# Interface_Adapter_Mk_2.net
KiCad netlist of a schematic drawn in EAGLE
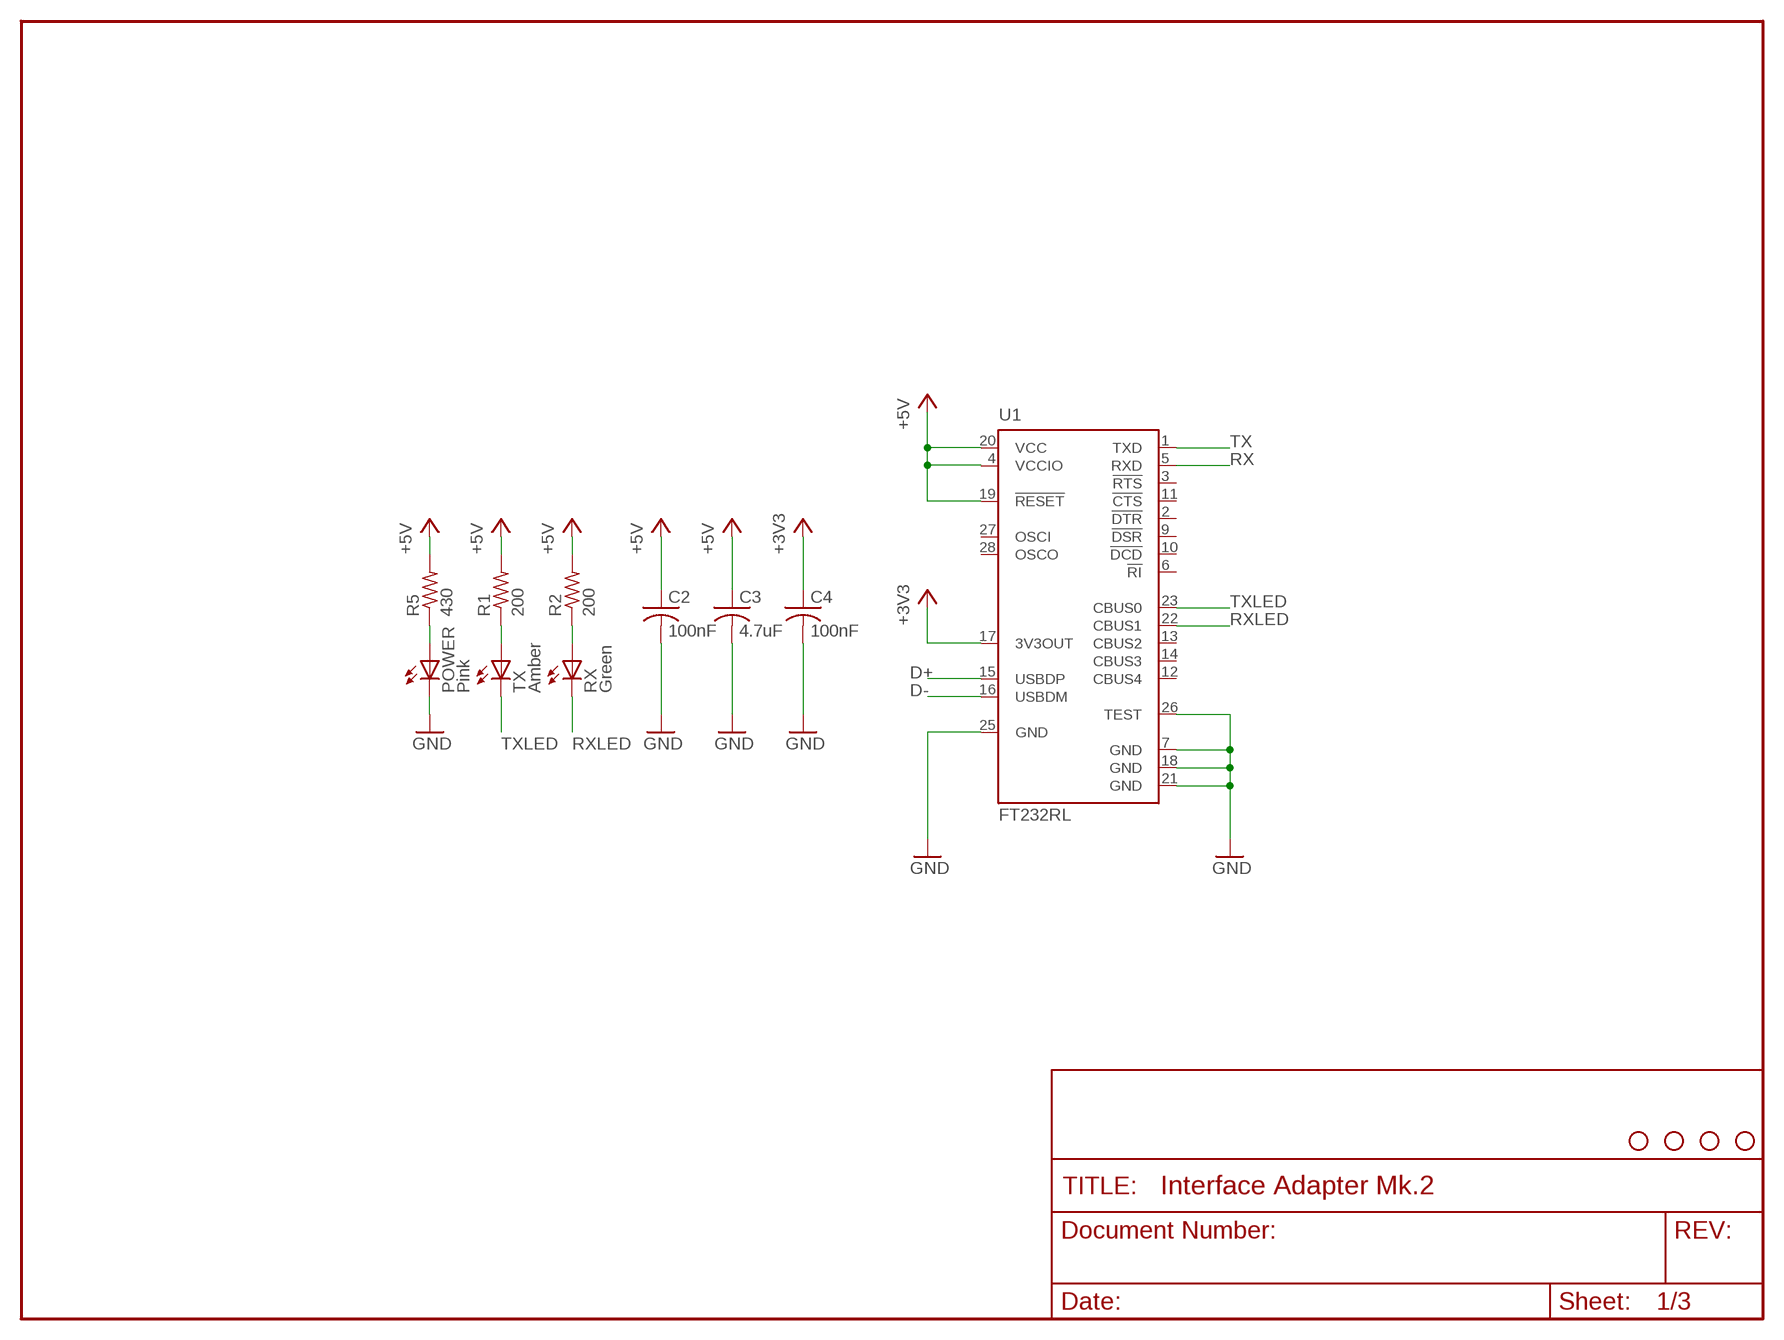
[diagram p0: schematic, sheet 1]
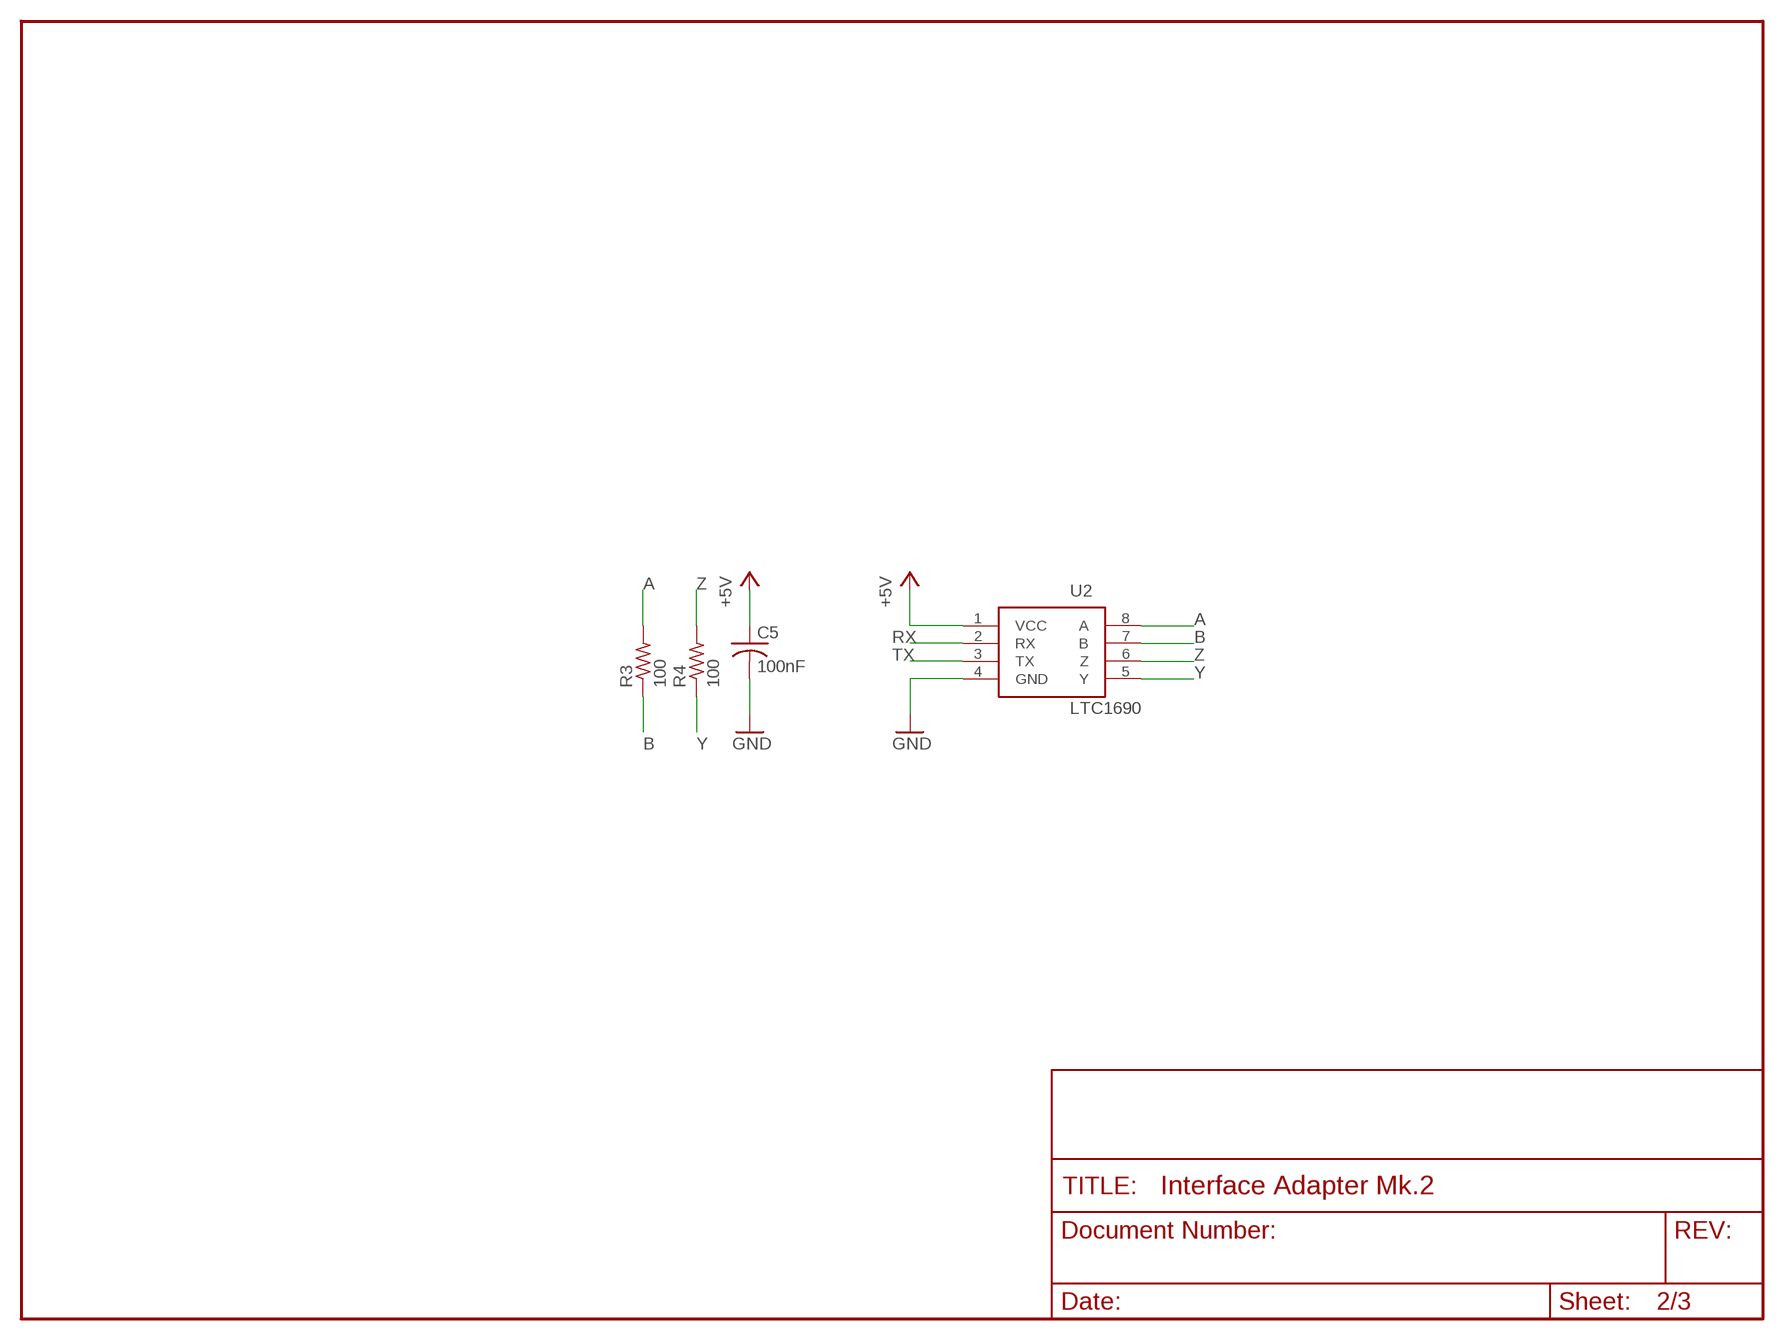
[diagram p1: schematic, sheet 2]
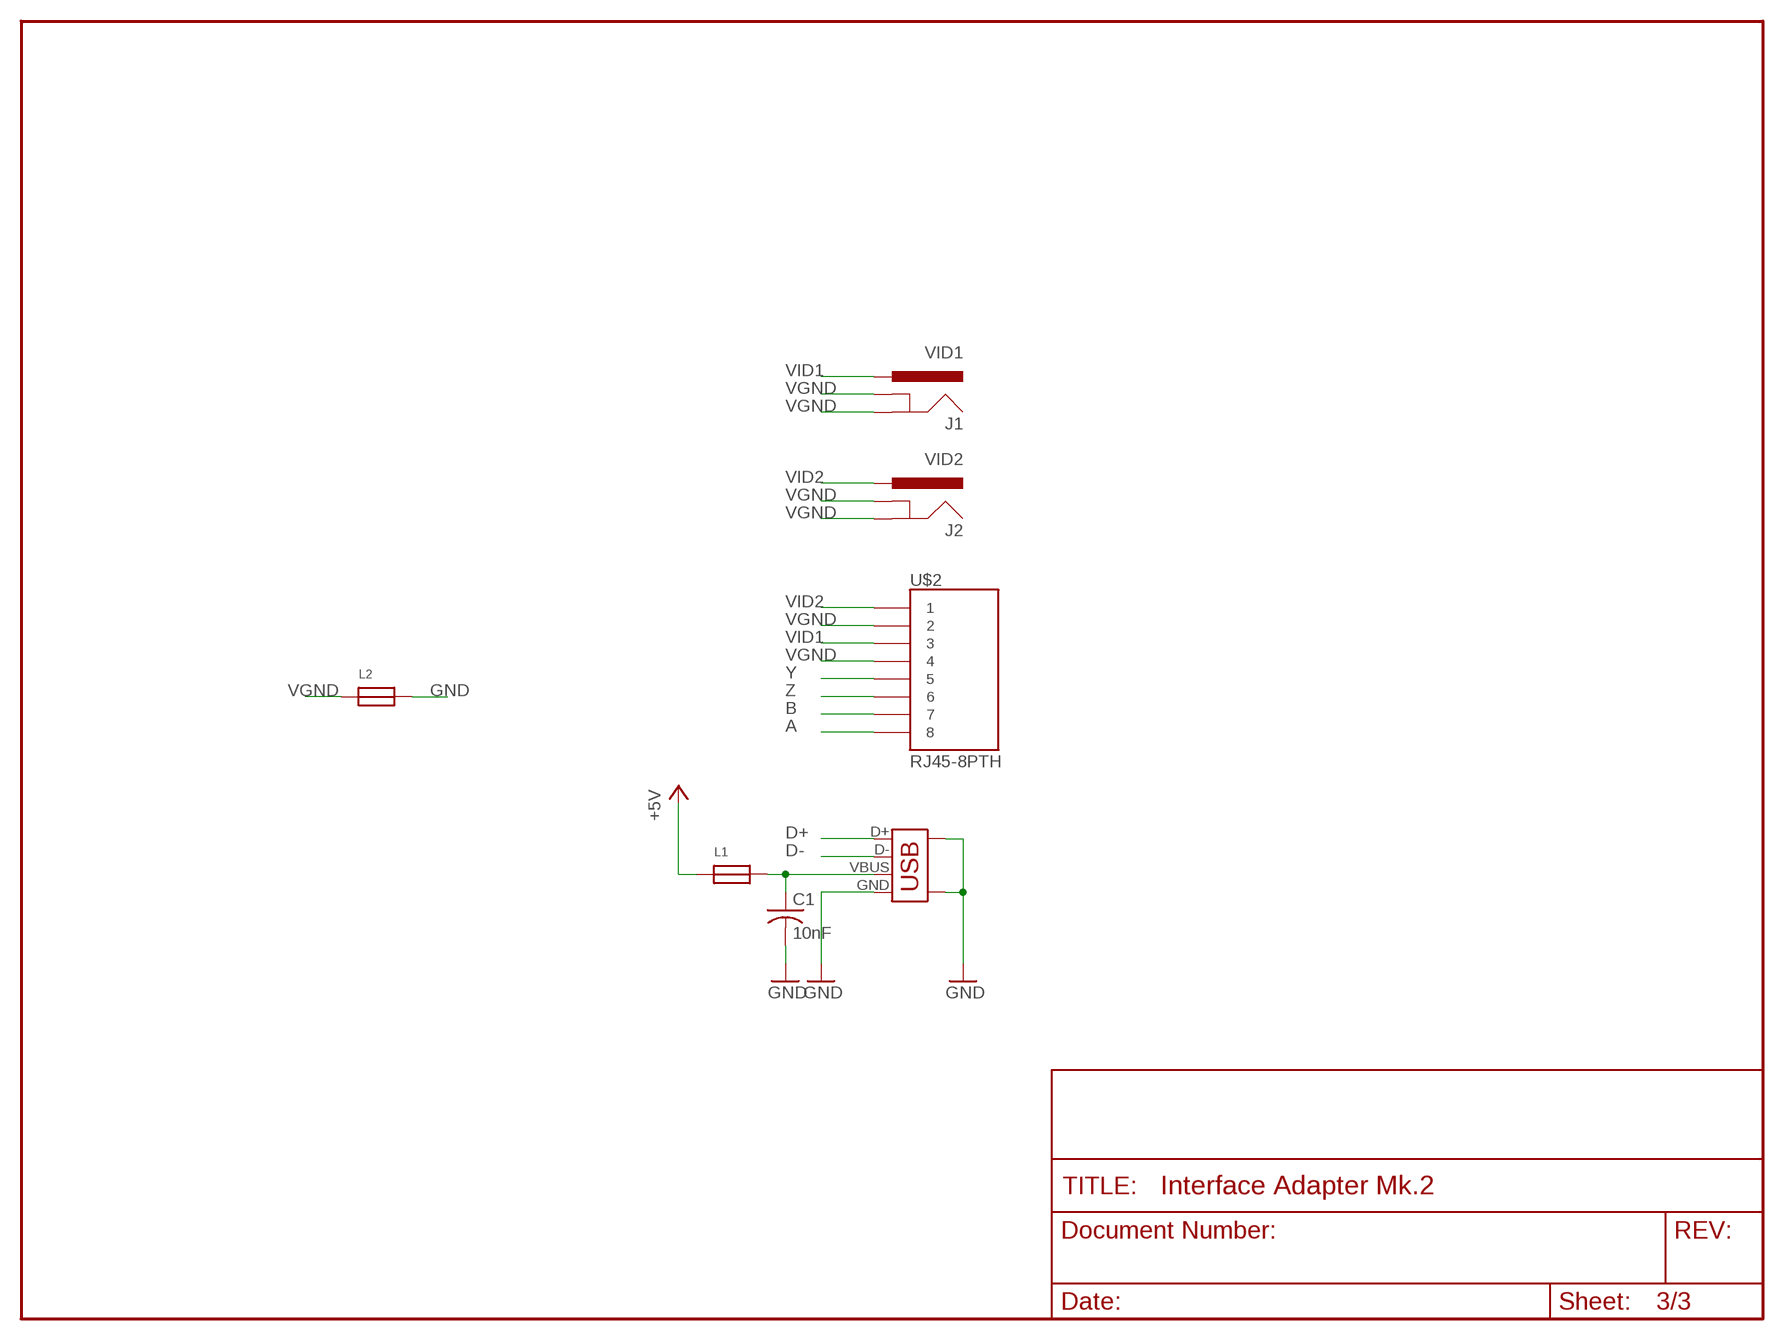
[diagram p2: schematic, sheet 3]

(export (version "E")
  (design (tool "Eeschema 10.0.6"))
  (components
    (comp (ref "C5")
      (value "100nF")
      (footprint "eagle-import:C0603")
      (libsource (lib "eagle-import") (part "C-USC0603"))
    )
    (comp (ref "R3")
      (value "100")
      (footprint "eagle-import:R0603")
      (libsource (lib "eagle-import") (part "R-US_R0603"))
    )
    (comp (ref "R4")
      (value "100")
      (footprint "eagle-import:R0603")
      (libsource (lib "eagle-import") (part "R-US_R0603"))
    )
    (comp (ref "U2")
      (value "LTC1690")
      (footprint "eagle-import:SOIC-8")
      (libsource (lib "eagle-import") (part "LTC1690"))
    )
    (comp (ref "C1")
      (value "10nF")
      (footprint "eagle-import:C0603")
      (libsource (lib "eagle-import") (part "C-USC0603"))
    )
    (comp (ref "J1")
      (value "VID1")
      (footprint "eagle-import:RCA")
      (libsource (lib "eagle-import") (part "POWER_JACKRCA"))
    )
    (comp (ref "J2")
      (value "VID2")
      (footprint "eagle-import:RCA")
      (libsource (lib "eagle-import") (part "POWER_JACKRCA"))
    )
    (comp (ref "L1")
      (value "FERRITE")
      (footprint "eagle-import:0603")
      (libsource (lib "eagle-import") (part "FERRITE"))
    )
    (comp (ref "L2")
      (value "FERRITE")
      (footprint "eagle-import:0603")
      (libsource (lib "eagle-import") (part "FERRITE"))
    )
    (comp (ref "U$2")
      (value "RJ45-8PTH")
      (footprint "eagle-import:RJ45-8")
      (libsource (lib "eagle-import") (part "RJ45-8PTH"))
    )
    (comp (ref "X1")
      (value "USBPTH")
      (footprint "eagle-import:USB-B-PTH")
      (libsource (lib "eagle-import") (part "USBPTH"))
    )
    (comp (ref "C2")
      (value "100nF")
      (footprint "eagle-import:C0603")
      (libsource (lib "eagle-import") (part "C-USC0603"))
    )
    (comp (ref "C3")
      (value "4.7uF")
      (footprint "eagle-import:C0603")
      (libsource (lib "eagle-import") (part "C-USC0603"))
    )
    (comp (ref "C4")
      (value "100nF")
      (footprint "eagle-import:C0603")
      (libsource (lib "eagle-import") (part "C-USC0603"))
    )
    (comp (ref "JP1")
      (value "STAND-OFF")
      (footprint "eagle-import:STAND-OFF")
      (libsource (lib "eagle-import") (part "STAND-OFF"))
    )
    (comp (ref "JP2")
      (value "STAND-OFF")
      (footprint "eagle-import:STAND-OFF")
      (libsource (lib "eagle-import") (part "STAND-OFF"))
    )
    (comp (ref "JP3")
      (value "STAND-OFF")
      (footprint "eagle-import:STAND-OFF")
      (libsource (lib "eagle-import") (part "STAND-OFF"))
    )
    (comp (ref "JP4")
      (value "STAND-OFF")
      (footprint "eagle-import:STAND-OFF")
      (libsource (lib "eagle-import") (part "STAND-OFF"))
    )
    (comp (ref "POWER")
      (value "Pink")
      (footprint "eagle-import:LED-0603")
      (libsource (lib "eagle-import") (part "LED0603"))
    )
    (comp (ref "R1")
      (value "200")
      (footprint "eagle-import:R0603")
      (libsource (lib "eagle-import") (part "R-US_R0603"))
    )
    (comp (ref "R2")
      (value "200")
      (footprint "eagle-import:R0603")
      (libsource (lib "eagle-import") (part "R-US_R0603"))
    )
    (comp (ref "R5")
      (value "430")
      (footprint "eagle-import:R0603")
      (libsource (lib "eagle-import") (part "R-US_R0603"))
    )
    (comp (ref "RX")
      (value "Green")
      (footprint "eagle-import:LED-0603")
      (libsource (lib "eagle-import") (part "LED0603"))
    )
    (comp (ref "TX")
      (value "Amber")
      (footprint "eagle-import:LED-0603")
      (libsource (lib "eagle-import") (part "LED0603"))
    )
    (comp (ref "U1")
      (value "FT232RL")
      (footprint "eagle-import:SSOP28")
      (libsource (lib "eagle-import") (part "FT232RL"))
    )
  )
  (nets
    (net (code "1") (name "+3V3") (class "Default")
      (node (ref "C4") (pin "1") (pinfunction "1_1") (pintype "passive"))
      (node (ref "U1") (pin "17") (pinfunction "3V3OUT_17") (pintype "output"))
    )
    (net (code "2") (name "+5V") (class "Default")
      (node (ref "C2") (pin "1") (pinfunction "1_1") (pintype "passive"))
      (node (ref "C3") (pin "1") (pinfunction "1_1") (pintype "passive"))
      (node (ref "C5") (pin "1") (pinfunction "1_1") (pintype "passive"))
      (node (ref "L1") (pin "1") (pinfunction "P$1_1") (pintype "bidirectional"))
      (node (ref "R1") (pin "2") (pinfunction "2_2") (pintype "passive"))
      (node (ref "R2") (pin "2") (pinfunction "2_2") (pintype "passive"))
      (node (ref "R5") (pin "2") (pinfunction "2_2") (pintype "passive"))
      (node (ref "U1") (pin "19") (pinfunction "~{RESET}_19") (pintype "input"))
      (node (ref "U1") (pin "20") (pinfunction "VCC_20") (pintype "power_in"))
      (node (ref "U1") (pin "4") (pinfunction "VCCIO_4") (pintype "power_in"))
      (node (ref "U2") (pin "1") (pinfunction "VCC_1") (pintype "bidirectional"))
    )
    (net (code "3") (name "A") (class "Default")
      (node (ref "R3") (pin "2") (pinfunction "2_2") (pintype "passive"))
      (node (ref "U$2") (pin "8") (pinfunction "8_8") (pintype "bidirectional"))
      (node (ref "U2") (pin "8") (pinfunction "A_8") (pintype "bidirectional"))
    )
    (net (code "4") (name "B") (class "Default")
      (node (ref "R3") (pin "1") (pinfunction "1_1") (pintype "passive"))
      (node (ref "U$2") (pin "7") (pinfunction "7_7") (pintype "bidirectional"))
      (node (ref "U2") (pin "7") (pinfunction "B_7") (pintype "bidirectional"))
    )
    (net (code "5") (name "D+") (class "Default")
      (node (ref "U1") (pin "15") (pinfunction "USBDP_15") (pintype "bidirectional"))
      (node (ref "X1") (pin "D+") (pinfunction "D+_D+") (pintype "bidirectional"))
    )
    (net (code "6") (name "D-") (class "Default")
      (node (ref "U1") (pin "16") (pinfunction "USBDM_16") (pintype "bidirectional"))
      (node (ref "X1") (pin "D-") (pinfunction "D-_D-") (pintype "bidirectional"))
    )
    (net (code "7") (name "GND") (class "Default")
      (node (ref "C1") (pin "2") (pinfunction "2_2") (pintype "passive"))
      (node (ref "C2") (pin "2") (pinfunction "2_2") (pintype "passive"))
      (node (ref "C3") (pin "2") (pinfunction "2_2") (pintype "passive"))
      (node (ref "C4") (pin "2") (pinfunction "2_2") (pintype "passive"))
      (node (ref "C5") (pin "2") (pinfunction "2_2") (pintype "passive"))
      (node (ref "L2") (pin "2") (pinfunction "P$2_2") (pintype "bidirectional"))
      (node (ref "POWER") (pin "C") (pinfunction "C_C") (pintype "passive"))
      (node (ref "U1") (pin "18") (pinfunction "GND_18") (pintype "power_in"))
      (node (ref "U1") (pin "21") (pinfunction "GND_21") (pintype "power_in"))
      (node (ref "U1") (pin "25") (pinfunction "GND_25") (pintype "power_in"))
      (node (ref "U1") (pin "26") (pinfunction "TEST_26") (pintype "input"))
      (node (ref "U1") (pin "7") (pinfunction "GND_7") (pintype "power_in"))
      (node (ref "U2") (pin "4") (pinfunction "GND_4") (pintype "bidirectional"))
      (node (ref "X1") (pin "GND") (pinfunction "GND_GND") (pintype "bidirectional"))
      (node (ref "X1") (pin "P$1") (pinfunction "P$1_P$1") (pintype "bidirectional"))
      (node (ref "X1") (pin "P$2") (pinfunction "P$2_P$2") (pintype "bidirectional"))
    )
    (net (code "8") (name "Net-(L1-P$2)") (class "Default")
      (node (ref "C1") (pin "1") (pinfunction "1_1") (pintype "passive"))
      (node (ref "L1") (pin "2") (pinfunction "P$2_2") (pintype "bidirectional"))
      (node (ref "X1") (pin "VBUS") (pinfunction "VBUS_VBUS") (pintype "bidirectional"))
    )
    (net (code "9") (name "Net-(POWER-PadA)") (class "Default")
      (node (ref "POWER") (pin "A") (pinfunction "A_A") (pintype "passive"))
      (node (ref "R5") (pin "1") (pinfunction "1_1") (pintype "passive"))
    )
    (net (code "10") (name "Net-(R1-Pad1)") (class "Default")
      (node (ref "R1") (pin "1") (pinfunction "1_1") (pintype "passive"))
      (node (ref "TX") (pin "A") (pinfunction "A_A") (pintype "passive"))
    )
    (net (code "11") (name "Net-(R2-Pad1)") (class "Default")
      (node (ref "R2") (pin "1") (pinfunction "1_1") (pintype "passive"))
      (node (ref "RX") (pin "A") (pinfunction "A_A") (pintype "passive"))
    )
    (net (code "12") (name "RX") (class "Default")
      (node (ref "U1") (pin "5") (pinfunction "RXD_5") (pintype "input"))
      (node (ref "U2") (pin "2") (pinfunction "RX_2") (pintype "bidirectional"))
    )
    (net (code "13") (name "RXLED") (class "Default")
      (node (ref "RX") (pin "C") (pinfunction "C_C") (pintype "passive"))
      (node (ref "U1") (pin "22") (pinfunction "CBUS1_22") (pintype "bidirectional"))
    )
    (net (code "14") (name "TX") (class "Default")
      (node (ref "U1") (pin "1") (pinfunction "TXD_1") (pintype "output"))
      (node (ref "U2") (pin "3") (pinfunction "TX_3") (pintype "bidirectional"))
    )
    (net (code "15") (name "TXLED") (class "Default")
      (node (ref "TX") (pin "C") (pinfunction "C_C") (pintype "passive"))
      (node (ref "U1") (pin "23") (pinfunction "CBUS0_23") (pintype "bidirectional"))
    )
    (net (code "16") (name "VGND") (class "Default")
      (node (ref "J1") (pin "BARREL") (pinfunction "GND_BARREL") (pintype "bidirectional"))
      (node (ref "J1") (pin "SPRING") (pinfunction "GNDBREAK_SPRING") (pintype "bidirectional"))
      (node (ref "J2") (pin "BARREL") (pinfunction "GND_BARREL") (pintype "bidirectional"))
      (node (ref "J2") (pin "SPRING") (pinfunction "GNDBREAK_SPRING") (pintype "bidirectional"))
      (node (ref "L2") (pin "1") (pinfunction "P$1_1") (pintype "bidirectional"))
      (node (ref "U$2") (pin "2") (pinfunction "2_2") (pintype "bidirectional"))
      (node (ref "U$2") (pin "4") (pinfunction "4_4") (pintype "bidirectional"))
    )
    (net (code "17") (name "VID1") (class "Default")
      (node (ref "J1") (pin "BREAK") (pinfunction "PWR_BREAK") (pintype "bidirectional"))
      (node (ref "U$2") (pin "3") (pinfunction "3_3") (pintype "bidirectional"))
    )
    (net (code "18") (name "VID2") (class "Default")
      (node (ref "J2") (pin "BREAK") (pinfunction "PWR_BREAK") (pintype "bidirectional"))
      (node (ref "U$2") (pin "1") (pinfunction "1_1") (pintype "bidirectional"))
    )
    (net (code "19") (name "Y") (class "Default")
      (node (ref "R4") (pin "1") (pinfunction "1_1") (pintype "passive"))
      (node (ref "U$2") (pin "5") (pinfunction "5_5") (pintype "bidirectional"))
      (node (ref "U2") (pin "5") (pinfunction "Y_5") (pintype "bidirectional"))
    )
    (net (code "20") (name "Z") (class "Default")
      (node (ref "R4") (pin "2") (pinfunction "2_2") (pintype "passive"))
      (node (ref "U$2") (pin "6") (pinfunction "6_6") (pintype "bidirectional"))
      (node (ref "U2") (pin "6") (pinfunction "Z_6") (pintype "bidirectional"))
    )
    (net (code "21") (name "unconnected-(U1-CBUS2-Pad13)") (class "Default")
      (node (ref "U1") (pin "13") (pinfunction "CBUS2_13") (pintype "bidirectional"))
    )
    (net (code "22") (name "unconnected-(U1-CBUS3-Pad14)") (class "Default")
      (node (ref "U1") (pin "14") (pinfunction "CBUS3_14") (pintype "bidirectional"))
    )
    (net (code "23") (name "unconnected-(U1-CBUS4-Pad12)") (class "Default")
      (node (ref "U1") (pin "12") (pinfunction "CBUS4_12") (pintype "bidirectional"))
    )
    (net (code "24") (name "unconnected-(U1-OSCI-Pad27)") (class "Default")
      (node (ref "U1") (pin "27") (pinfunction "OSCI_27") (pintype "input"))
    )
    (net (code "25") (name "unconnected-(U1-OSCO-Pad28)") (class "Default")
      (node (ref "U1") (pin "28") (pinfunction "OSCO_28") (pintype "output"))
    )
    (net (code "26") (name "unconnected-(U1-~{CTS}-Pad11)") (class "Default")
      (node (ref "U1") (pin "11") (pinfunction "~{CTS}_11") (pintype "input"))
    )
    (net (code "27") (name "unconnected-(U1-~{DCD}-Pad10)") (class "Default")
      (node (ref "U1") (pin "10") (pinfunction "~{DCD}_10") (pintype "input"))
    )
    (net (code "28") (name "unconnected-(U1-~{DSR}-Pad9)") (class "Default")
      (node (ref "U1") (pin "9") (pinfunction "~{DSR}_9") (pintype "input"))
    )
    (net (code "29") (name "unconnected-(U1-~{DTR}-Pad2)") (class "Default")
      (node (ref "U1") (pin "2") (pinfunction "~{DTR}_2") (pintype "output"))
    )
    (net (code "30") (name "unconnected-(U1-~{RI}-Pad6)") (class "Default")
      (node (ref "U1") (pin "6") (pinfunction "~{RI}_6") (pintype "input"))
    )
    (net (code "31") (name "unconnected-(U1-~{RTS}-Pad3)") (class "Default")
      (node (ref "U1") (pin "3") (pinfunction "~{RTS}_3") (pintype "output"))
    )
  )
)
